# LcsNodes-Extension-GPIO-Board-32-S-B_00_.net
KiCad netlist of a schematic drawn in EasyEDA
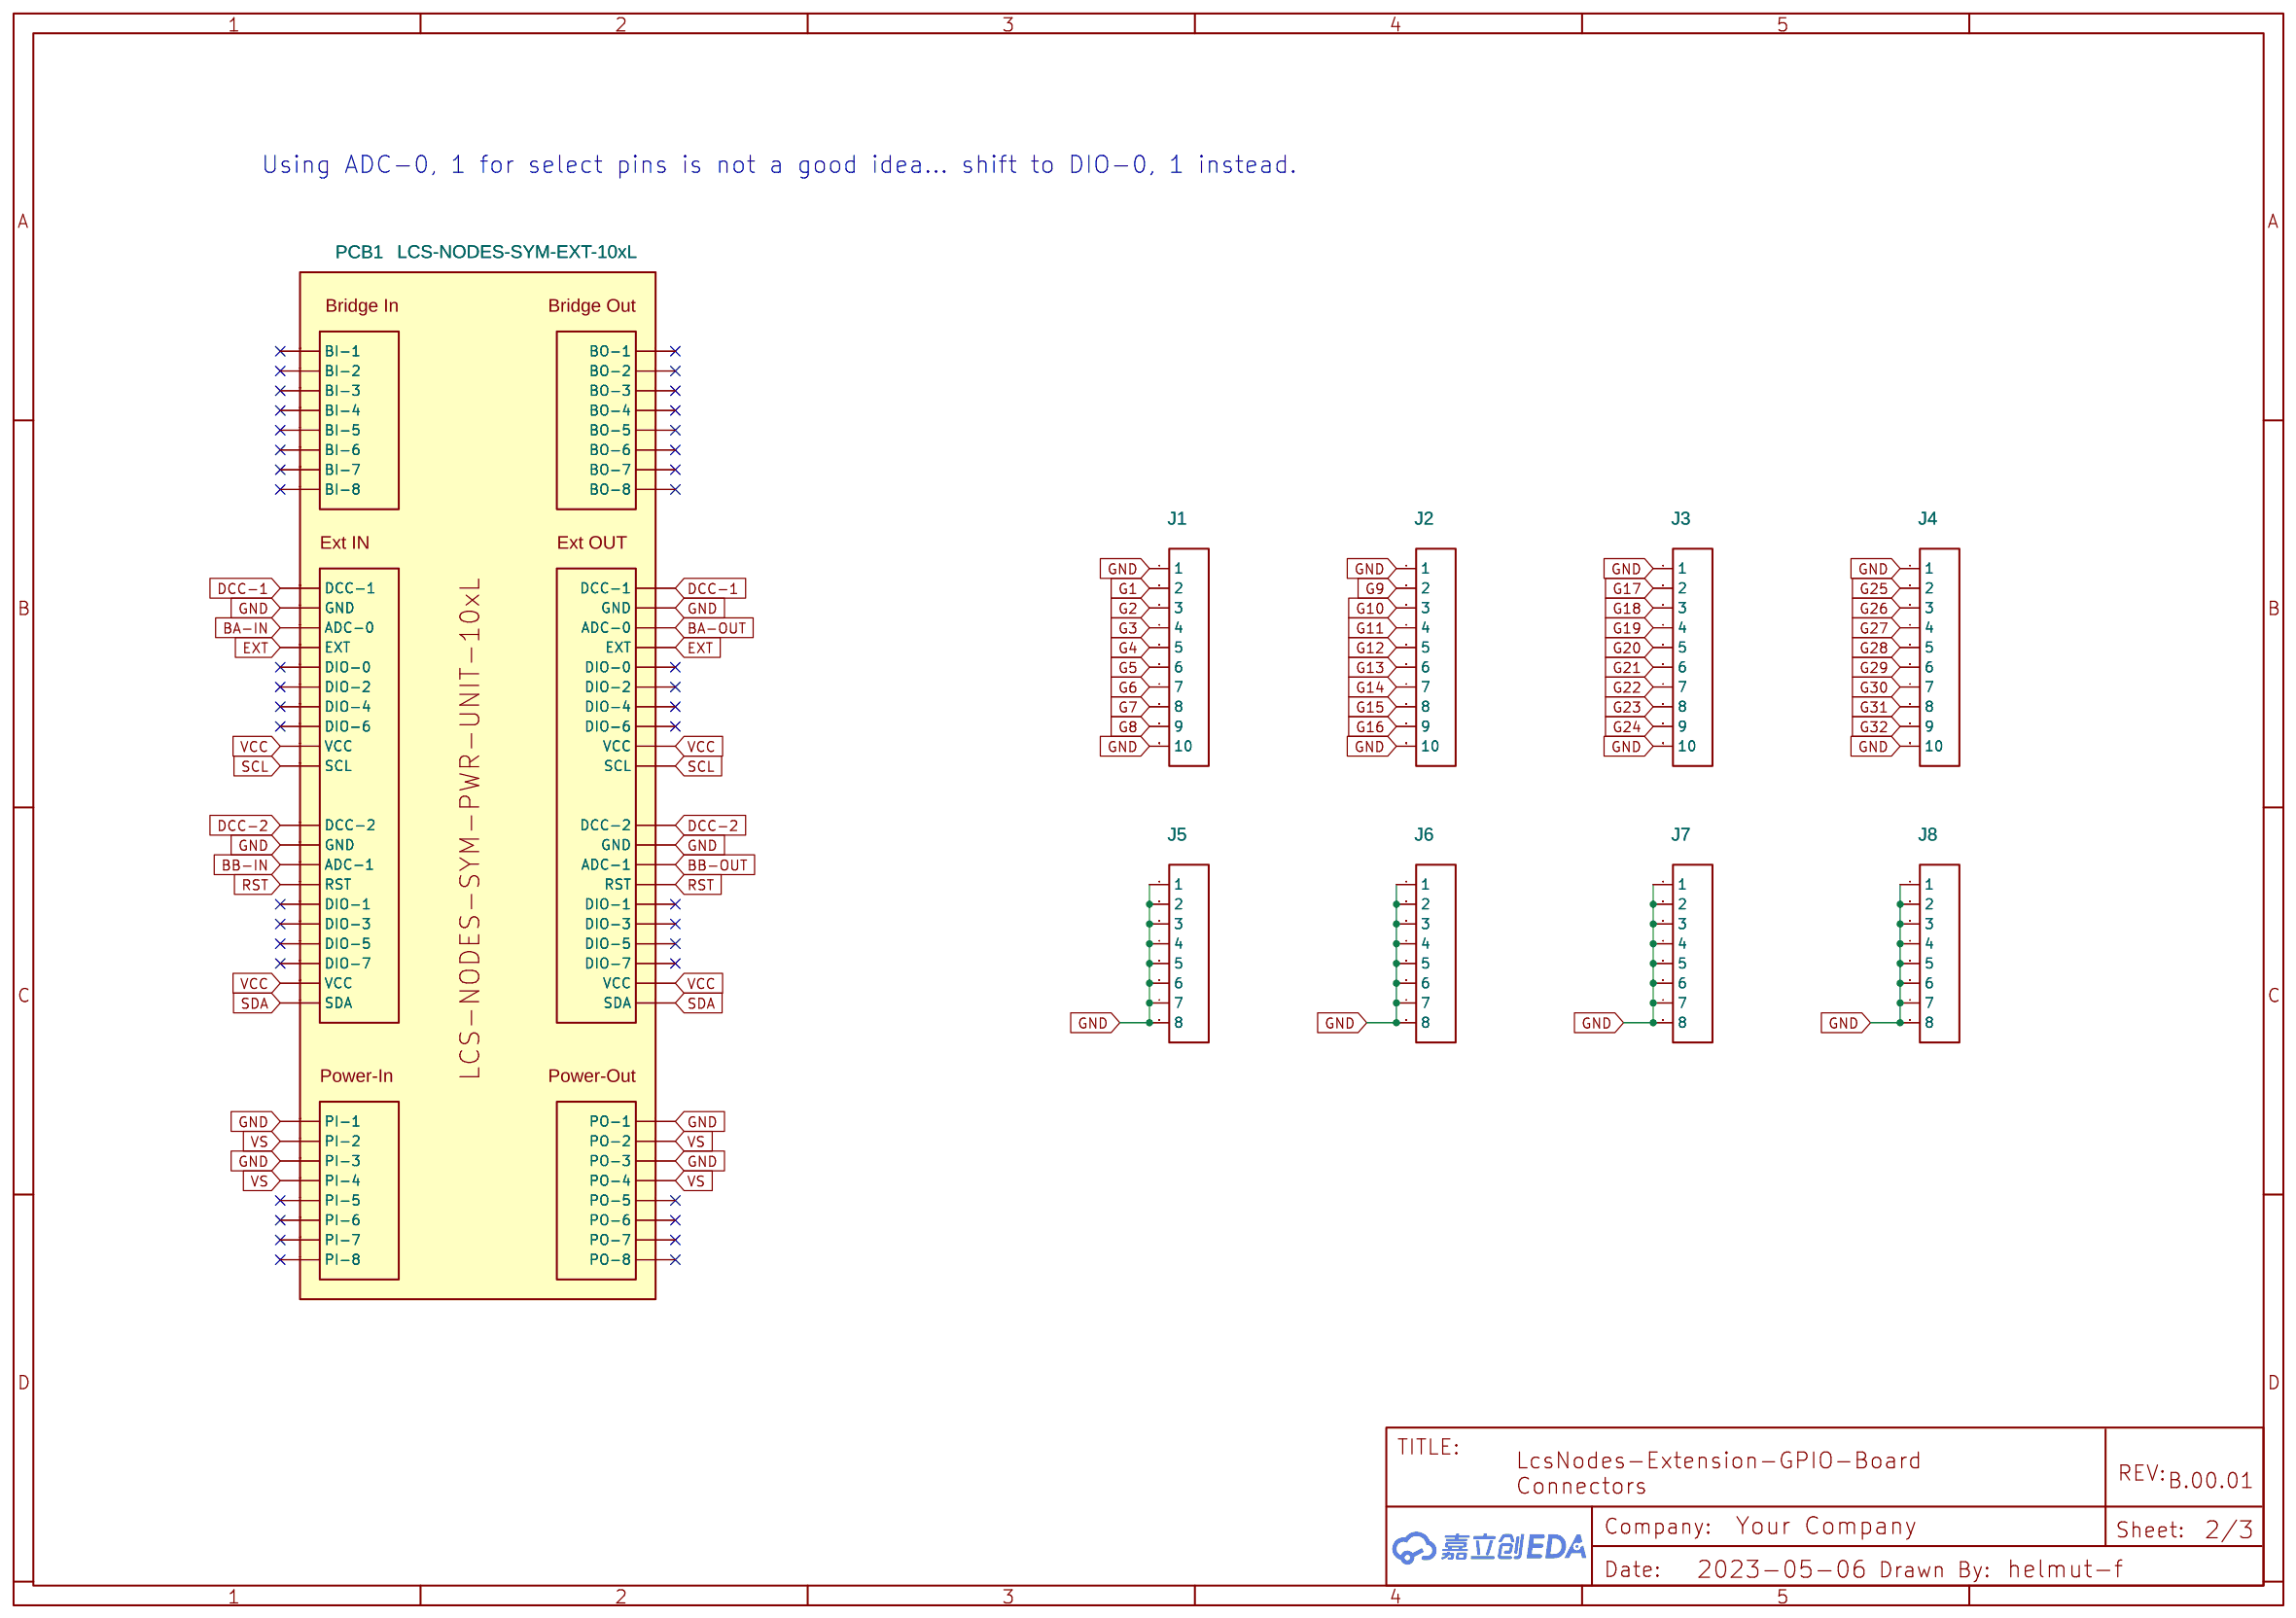
[diagram p0: Connectors]
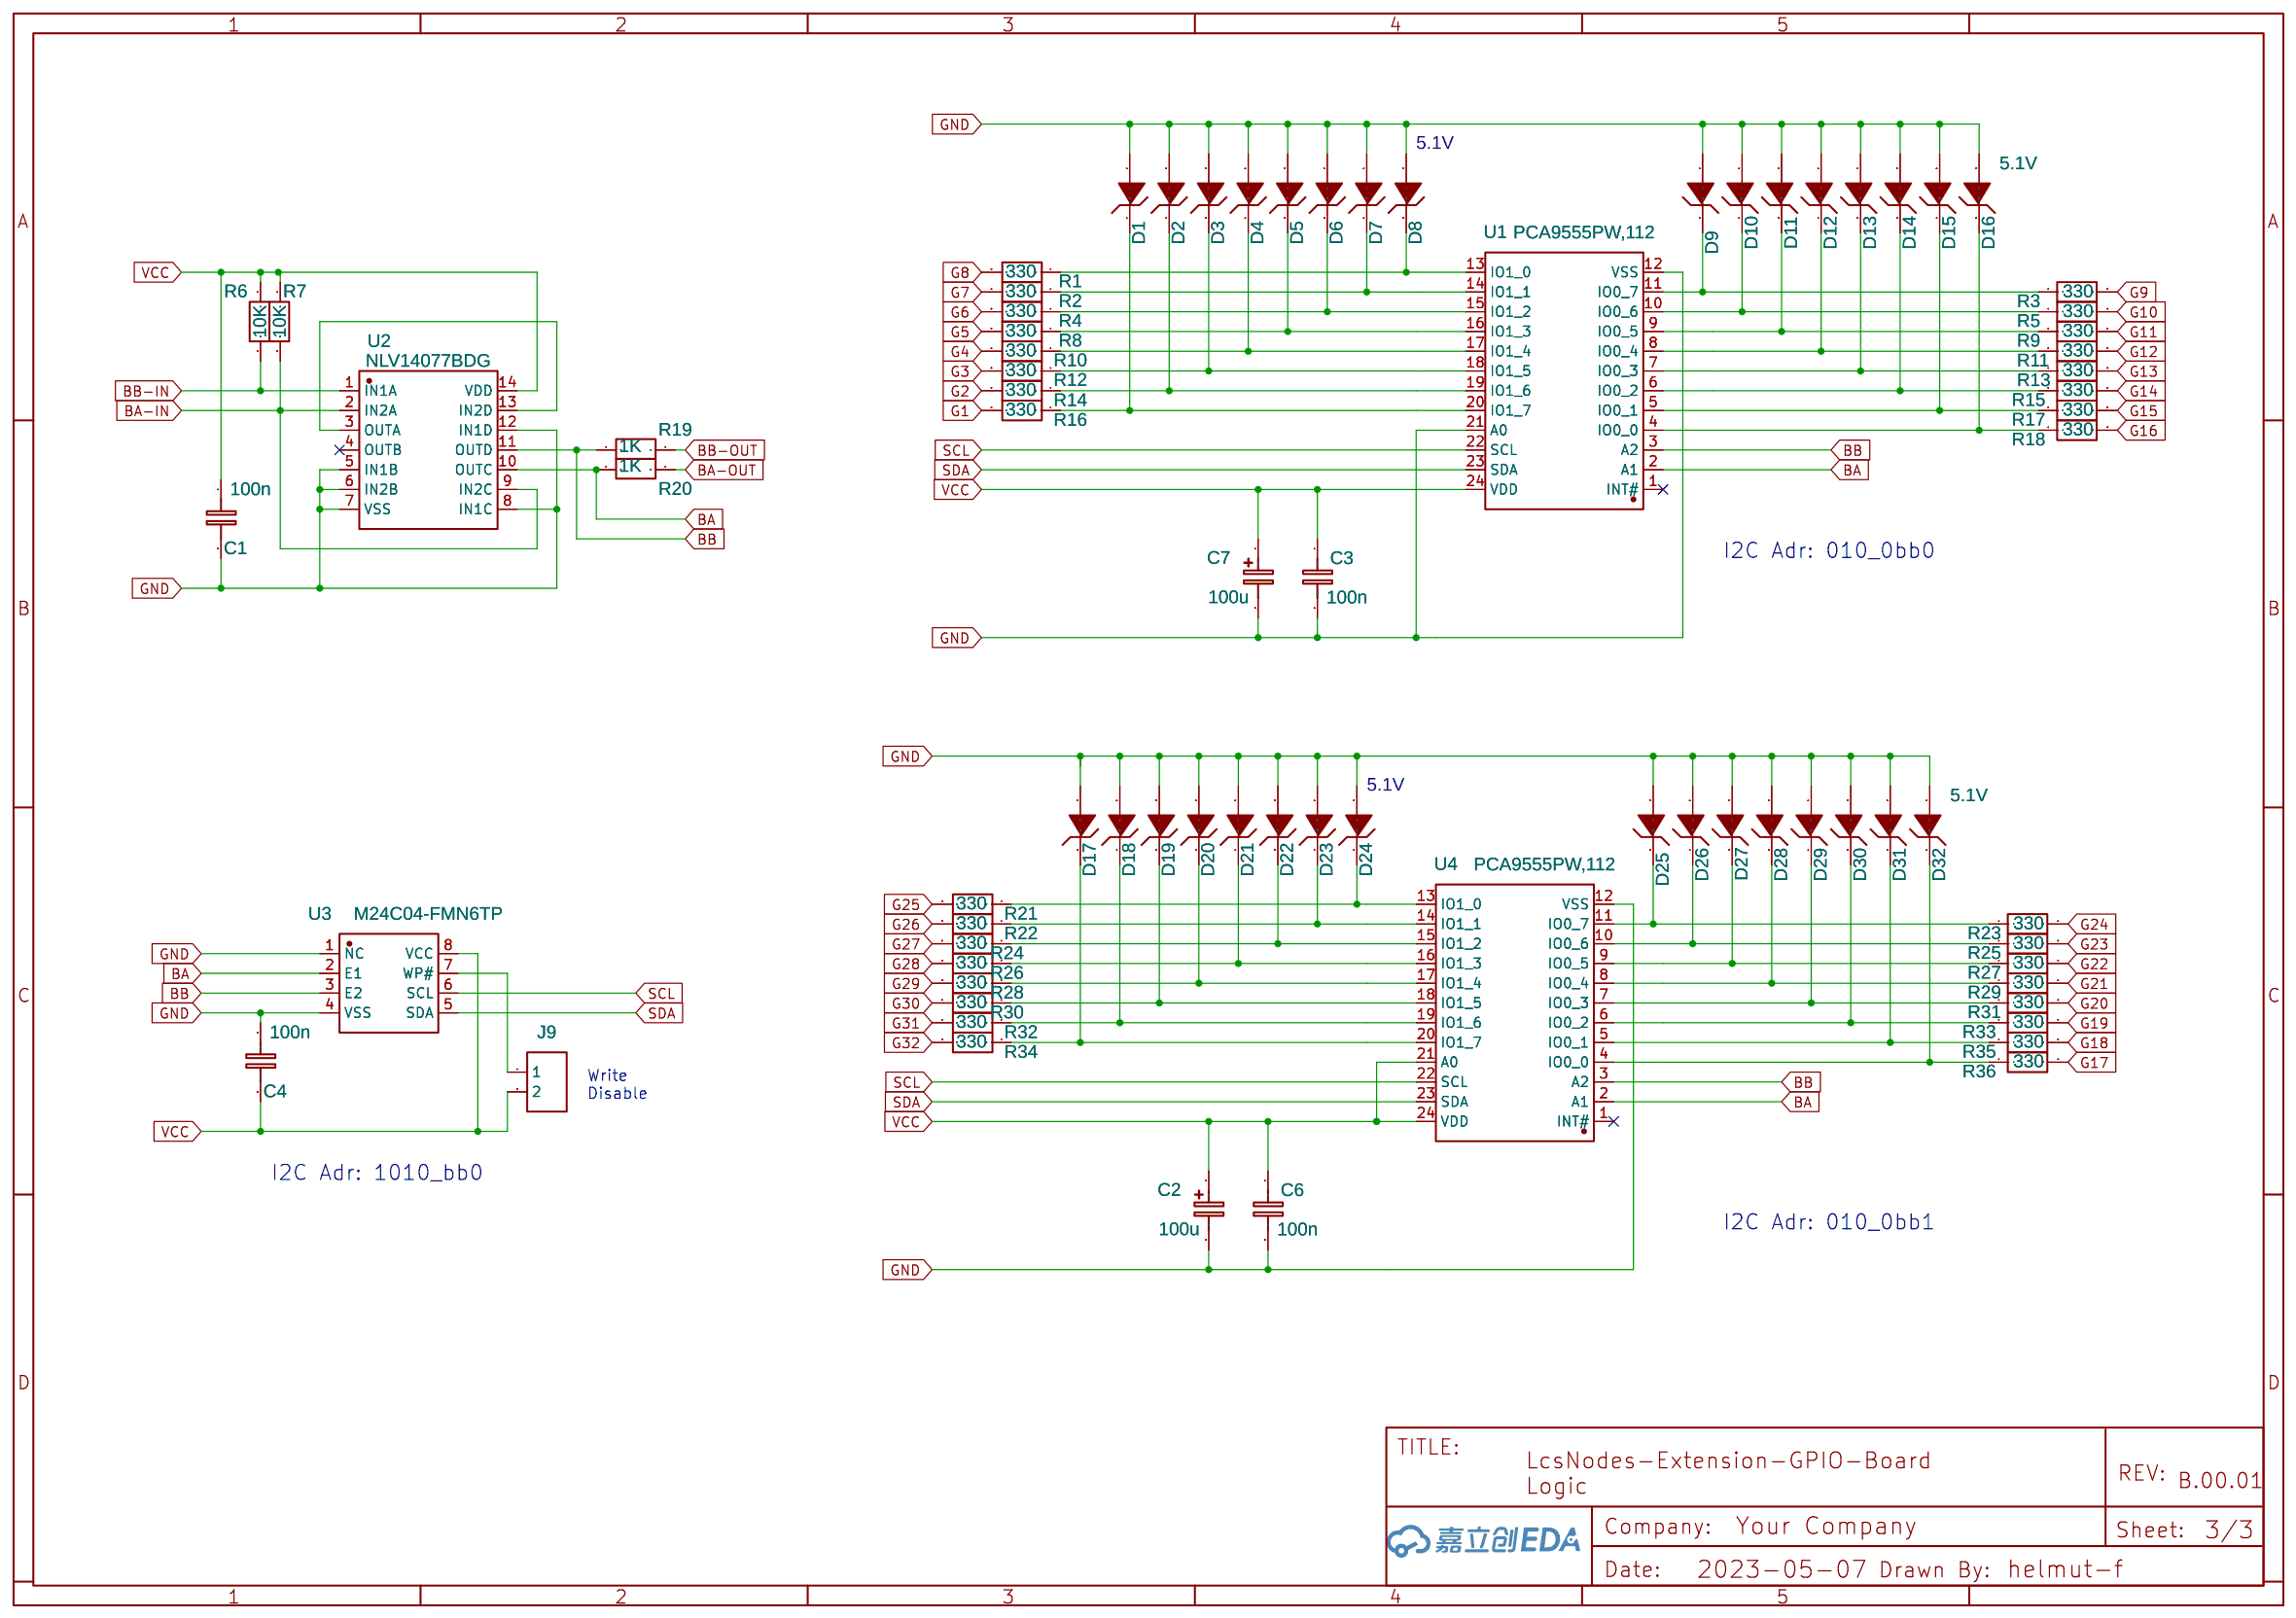
[diagram p1: Logic]
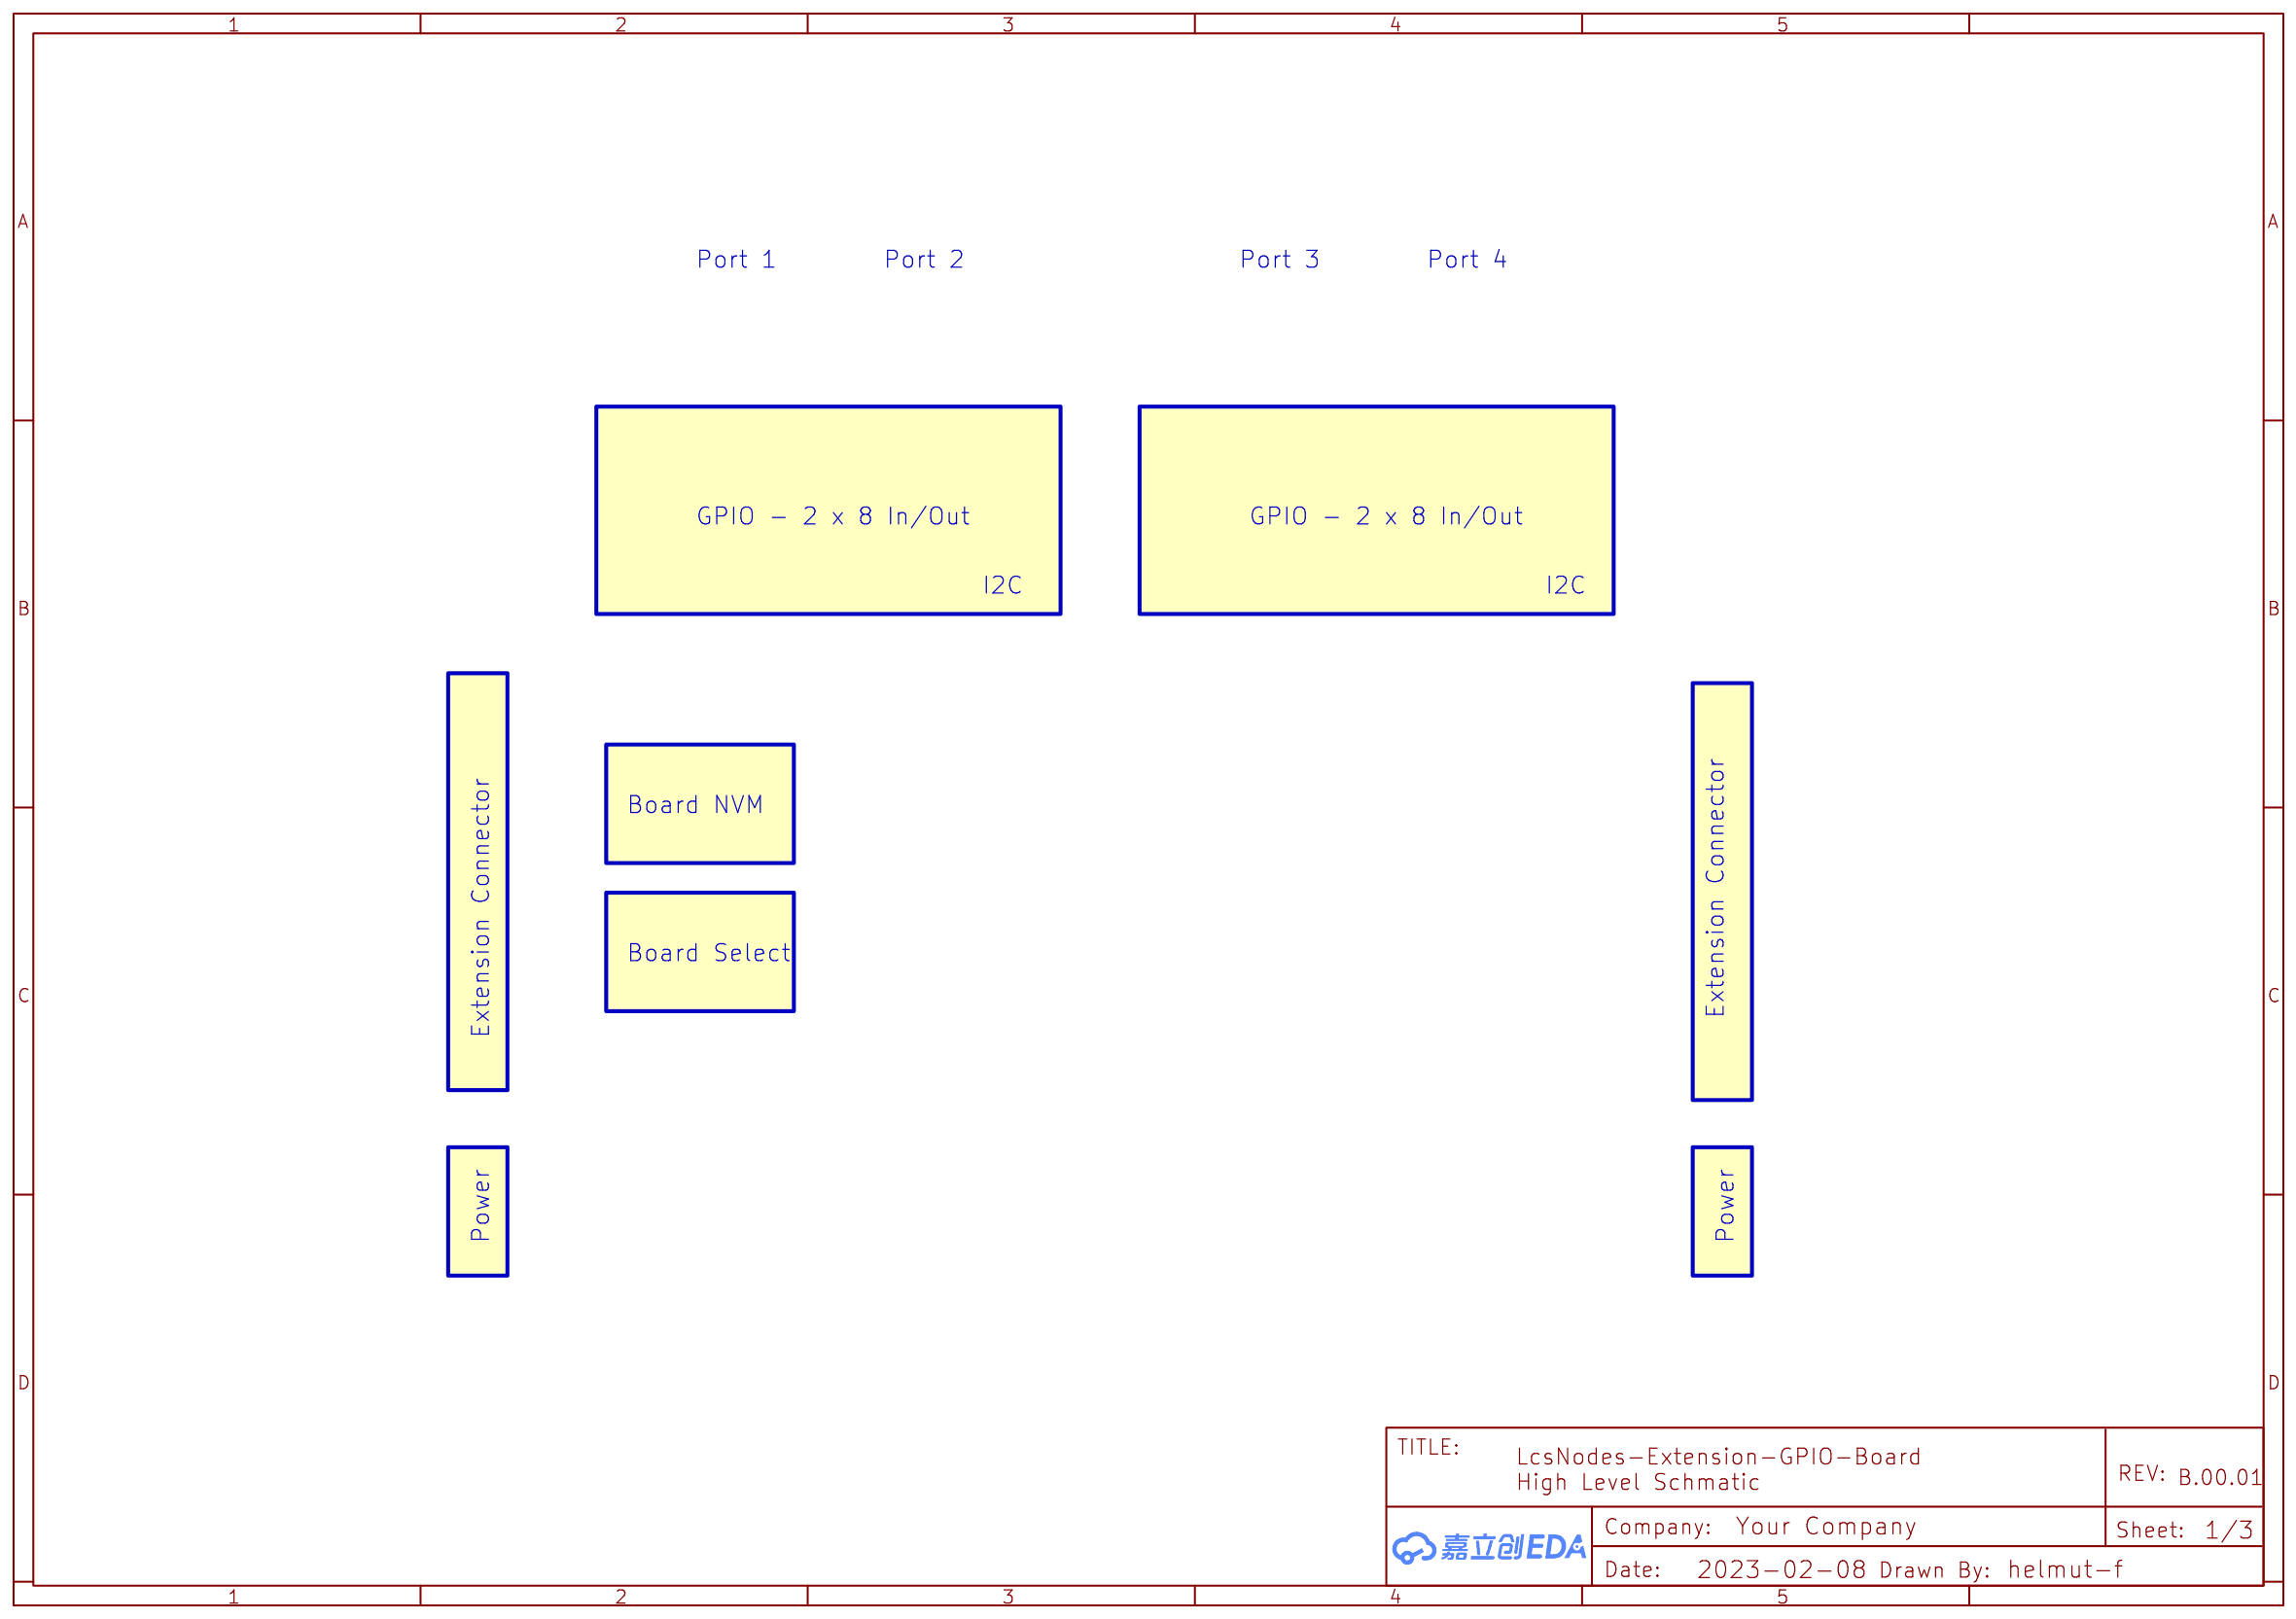
[diagram p2: High Level Schematic]

(export (version "E")
  (design (tool "Eeschema 10.0.6"))
  (components
    (comp (ref "J1") (value "HDR-M-2.54_1x10") (libsource (lib "") (part "HDR-M-2.54_1x10")))
    (comp (ref "J2") (value "HDR-M-2.54_1x10") (libsource (lib "") (part "HDR-M-2.54_1x10")))
    (comp (ref "J3") (value "HDR-M-2.54_1x10") (libsource (lib "") (part "HDR-M-2.54_1x10")))
    (comp (ref "J4") (value "HDR-M-2.54_1x10") (libsource (lib "") (part "HDR-M-2.54_1x10")))
    (comp (ref "J5") (value "HDR-M-2.54_1x8") (libsource (lib "") (part "HDR-M-2.54_1x8")))
    (comp (ref "J6") (value "HDR-M-2.54_1x8") (libsource (lib "") (part "HDR-M-2.54_1x8")))
    (comp (ref "J7") (value "HDR-M-2.54_1x8") (libsource (lib "") (part "HDR-M-2.54_1x8")))
    (comp (ref "J8") (value "HDR-M-2.54_1x8") (libsource (lib "") (part "HDR-M-2.54_1x8")))
    (comp (ref "PCB1") (value "LCS-NODES-SYM-EXT-10xL") (libsource (lib "") (part "LCS-NODES-SYM-EXT-10xL")))
    (comp (ref "C1") (value "100n") (libsource (lib "") (part "C_0603_EU_1")))
    (comp (ref "C2") (value "100u") (libsource (lib "") (part "CE_TH_D4.0×F1.5_EU")))
    (comp (ref "C3") (value "100n") (libsource (lib "") (part "C_0603_EU_1")))
    (comp (ref "C4") (value "100n") (libsource (lib "") (part "C_0603_EU")))
    (comp (ref "C6") (value "100n") (libsource (lib "") (part "C_0603_EU")))
    (comp (ref "C7") (value "100u") (libsource (lib "") (part "CE_TH_D4.0×F1.5_EU_1")))
    (comp (ref "D1")
      (value "5.1V")
      (fields (field (name "Manufacturer Part") "Diode Zener") (field (name "Manufacturer") "SEMTECH"))
      (libsource (lib "") (part "Diode Zener"))
    )
    (comp (ref "D2")
      (value "5.1V")
      (fields (field (name "Manufacturer Part") "Diode Zener") (field (name "Manufacturer") "SEMTECH"))
      (libsource (lib "") (part "Diode Zener"))
    )
    (comp (ref "D3")
      (value "5.1V")
      (fields (field (name "Manufacturer Part") "Diode Zener") (field (name "Manufacturer") "SEMTECH"))
      (libsource (lib "") (part "Diode Zener"))
    )
    (comp (ref "D4")
      (value "5.1V")
      (fields (field (name "Manufacturer Part") "Diode Zener") (field (name "Manufacturer") "SEMTECH"))
      (libsource (lib "") (part "Diode Zener"))
    )
    (comp (ref "D5")
      (value "5.1V")
      (fields (field (name "Manufacturer Part") "Diode Zener") (field (name "Manufacturer") "SEMTECH"))
      (libsource (lib "") (part "Diode Zener"))
    )
    (comp (ref "D6")
      (value "5.1V")
      (fields (field (name "Manufacturer Part") "Diode Zener") (field (name "Manufacturer") "SEMTECH"))
      (libsource (lib "") (part "Diode Zener"))
    )
    (comp (ref "D7")
      (value "5.1V")
      (fields (field (name "Manufacturer Part") "Diode Zener") (field (name "Manufacturer") "SEMTECH"))
      (libsource (lib "") (part "Diode Zener"))
    )
    (comp (ref "D8")
      (value "5.1V")
      (fields (field (name "Manufacturer Part") "Diode Zener") (field (name "Manufacturer") "SEMTECH"))
      (libsource (lib "") (part "Diode Zener"))
    )
    (comp (ref "D9")
      (value "5.1V")
      (fields (field (name "Manufacturer Part") "Diode Zener") (field (name "Manufacturer") "SEMTECH"))
      (libsource (lib "") (part "Diode Zener_1"))
    )
    (comp (ref "D10")
      (value "5.1V")
      (fields (field (name "Manufacturer Part") "Diode Zener") (field (name "Manufacturer") "SEMTECH"))
      (libsource (lib "") (part "Diode Zener_1"))
    )
    (comp (ref "D11")
      (value "5.1V")
      (fields (field (name "Manufacturer Part") "Diode Zener") (field (name "Manufacturer") "SEMTECH"))
      (libsource (lib "") (part "Diode Zener_1"))
    )
    (comp (ref "D12")
      (value "5.1V")
      (fields (field (name "Manufacturer Part") "Diode Zener") (field (name "Manufacturer") "SEMTECH"))
      (libsource (lib "") (part "Diode Zener_1"))
    )
    (comp (ref "D13")
      (value "5.1V")
      (fields (field (name "Manufacturer Part") "Diode Zener") (field (name "Manufacturer") "SEMTECH"))
      (libsource (lib "") (part "Diode Zener_1"))
    )
    (comp (ref "D14")
      (value "5.1V")
      (fields (field (name "Manufacturer Part") "Diode Zener") (field (name "Manufacturer") "SEMTECH"))
      (libsource (lib "") (part "Diode Zener_1"))
    )
    (comp (ref "D15")
      (value "5.1V")
      (fields (field (name "Manufacturer Part") "Diode Zener") (field (name "Manufacturer") "SEMTECH"))
      (libsource (lib "") (part "Diode Zener_1"))
    )
    (comp (ref "D16")
      (value "5.1V")
      (fields (field (name "Manufacturer Part") "Diode Zener") (field (name "Manufacturer") "SEMTECH"))
      (libsource (lib "") (part "Diode Zener_1"))
    )
    (comp (ref "D17")
      (value "5.1V")
      (fields (field (name "Manufacturer Part") "Diode Zener") (field (name "Manufacturer") "SEMTECH"))
      (libsource (lib "") (part "Diode Zener"))
    )
    (comp (ref "D18")
      (value "5.1V")
      (fields (field (name "Manufacturer Part") "Diode Zener") (field (name "Manufacturer") "SEMTECH"))
      (libsource (lib "") (part "Diode Zener"))
    )
    (comp (ref "D19")
      (value "5.1V")
      (fields (field (name "Manufacturer Part") "Diode Zener") (field (name "Manufacturer") "SEMTECH"))
      (libsource (lib "") (part "Diode Zener"))
    )
    (comp (ref "D20")
      (value "5.1V")
      (fields (field (name "Manufacturer Part") "Diode Zener") (field (name "Manufacturer") "SEMTECH"))
      (libsource (lib "") (part "Diode Zener"))
    )
    (comp (ref "D21")
      (value "5.1V")
      (fields (field (name "Manufacturer Part") "Diode Zener") (field (name "Manufacturer") "SEMTECH"))
      (libsource (lib "") (part "Diode Zener"))
    )
    (comp (ref "D22")
      (value "5.1V")
      (fields (field (name "Manufacturer Part") "Diode Zener") (field (name "Manufacturer") "SEMTECH"))
      (libsource (lib "") (part "Diode Zener"))
    )
    (comp (ref "D23")
      (value "5.1V")
      (fields (field (name "Manufacturer Part") "Diode Zener") (field (name "Manufacturer") "SEMTECH"))
      (libsource (lib "") (part "Diode Zener"))
    )
    (comp (ref "D24")
      (value "5.1V")
      (fields (field (name "Manufacturer Part") "Diode Zener") (field (name "Manufacturer") "SEMTECH"))
      (libsource (lib "") (part "Diode Zener"))
    )
    (comp (ref "D25")
      (value "5.1V")
      (fields (field (name "Manufacturer Part") "Diode Zener") (field (name "Manufacturer") "SEMTECH"))
      (libsource (lib "") (part "Diode Zener_1"))
    )
    (comp (ref "D26")
      (value "5.1V")
      (fields (field (name "Manufacturer Part") "Diode Zener") (field (name "Manufacturer") "SEMTECH"))
      (libsource (lib "") (part "Diode Zener_1"))
    )
    (comp (ref "D27")
      (value "5.1V")
      (fields (field (name "Manufacturer Part") "Diode Zener") (field (name "Manufacturer") "SEMTECH"))
      (libsource (lib "") (part "Diode Zener_1"))
    )
    (comp (ref "D28")
      (value "5.1V")
      (fields (field (name "Manufacturer Part") "Diode Zener") (field (name "Manufacturer") "SEMTECH"))
      (libsource (lib "") (part "Diode Zener_1"))
    )
    (comp (ref "D29")
      (value "5.1V")
      (fields (field (name "Manufacturer Part") "Diode Zener") (field (name "Manufacturer") "SEMTECH"))
      (libsource (lib "") (part "Diode Zener_1"))
    )
    (comp (ref "D30")
      (value "5.1V")
      (fields (field (name "Manufacturer Part") "Diode Zener") (field (name "Manufacturer") "SEMTECH"))
      (libsource (lib "") (part "Diode Zener_1"))
    )
    (comp (ref "D31")
      (value "5.1V")
      (fields (field (name "Manufacturer Part") "Diode Zener") (field (name "Manufacturer") "SEMTECH"))
      (libsource (lib "") (part "Diode Zener_1"))
    )
    (comp (ref "D32")
      (value "5.1V")
      (fields (field (name "Manufacturer Part") "Diode Zener") (field (name "Manufacturer") "SEMTECH"))
      (libsource (lib "") (part "Diode Zener_1"))
    )
    (comp (ref "J9") (value "HDR-M-2.54_1x2") (libsource (lib "") (part "HDR-M-2.54_1x2")))
    (comp (ref "R1") (value "330") (libsource (lib "") (part "R_AXIAL-0.3_EU_2")))
    (comp (ref "R2") (value "330") (libsource (lib "") (part "R_AXIAL-0.3_EU_2")))
    (comp (ref "R3") (value "330") (libsource (lib "") (part "R_AXIAL-0.3_EU_1")))
    (comp (ref "R4") (value "330") (libsource (lib "") (part "R_AXIAL-0.3_EU_2")))
    (comp (ref "R5") (value "330") (libsource (lib "") (part "R_AXIAL-0.3_EU_1")))
    (comp (ref "R6") (value "10K") (libsource (lib "") (part "R_AXIAL-0.3_EU")))
    (comp (ref "R7") (value "10K") (libsource (lib "") (part "R_AXIAL-0.3_EU")))
    (comp (ref "R8") (value "330") (libsource (lib "") (part "R_AXIAL-0.3_EU_2")))
    (comp (ref "R9") (value "330") (libsource (lib "") (part "R_AXIAL-0.3_EU_1")))
    (comp (ref "R10") (value "330") (libsource (lib "") (part "R_AXIAL-0.3_EU_2")))
    (comp (ref "R11") (value "330") (libsource (lib "") (part "R_AXIAL-0.3_EU_1")))
    (comp (ref "R12") (value "330") (libsource (lib "") (part "R_AXIAL-0.3_EU_2")))
    (comp (ref "R13") (value "330") (libsource (lib "") (part "R_AXIAL-0.3_EU_1")))
    (comp (ref "R14") (value "330") (libsource (lib "") (part "R_AXIAL-0.3_EU_2")))
    (comp (ref "R15") (value "330") (libsource (lib "") (part "R_AXIAL-0.3_EU_1")))
    (comp (ref "R16") (value "330") (libsource (lib "") (part "R_AXIAL-0.3_EU_2")))
    (comp (ref "R17") (value "330") (libsource (lib "") (part "R_AXIAL-0.3_EU_1")))
    (comp (ref "R18") (value "330") (libsource (lib "") (part "R_AXIAL-0.3_EU_1")))
    (comp (ref "R19") (value "1K") (libsource (lib "") (part "R_AXIAL-0.3_EU_3")))
    (comp (ref "R20") (value "1K") (libsource (lib "") (part "R_AXIAL-0.3_EU_3")))
    (comp (ref "R21") (value "330") (libsource (lib "") (part "R_AXIAL-0.3_EU_2")))
    (comp (ref "R22") (value "330") (libsource (lib "") (part "R_AXIAL-0.3_EU_2")))
    (comp (ref "R23") (value "330") (libsource (lib "") (part "R_AXIAL-0.3_EU_1")))
    (comp (ref "R24") (value "330") (libsource (lib "") (part "R_AXIAL-0.3_EU_2")))
    (comp (ref "R25") (value "330") (libsource (lib "") (part "R_AXIAL-0.3_EU_1")))
    (comp (ref "R26") (value "330") (libsource (lib "") (part "R_AXIAL-0.3_EU_2")))
    (comp (ref "R27") (value "330") (libsource (lib "") (part "R_AXIAL-0.3_EU_1")))
    (comp (ref "R28") (value "330") (libsource (lib "") (part "R_AXIAL-0.3_EU_2")))
    (comp (ref "R29") (value "330") (libsource (lib "") (part "R_AXIAL-0.3_EU_1")))
    (comp (ref "R30") (value "330") (libsource (lib "") (part "R_AXIAL-0.3_EU_2")))
    (comp (ref "R31") (value "330") (libsource (lib "") (part "R_AXIAL-0.3_EU_1")))
    (comp (ref "R32") (value "330") (libsource (lib "") (part "R_AXIAL-0.3_EU_2")))
    (comp (ref "R33") (value "330") (libsource (lib "") (part "R_AXIAL-0.3_EU_1")))
    (comp (ref "R34") (value "330") (libsource (lib "") (part "R_AXIAL-0.3_EU_2")))
    (comp (ref "R35") (value "330") (libsource (lib "") (part "R_AXIAL-0.3_EU_1")))
    (comp (ref "R36") (value "330") (libsource (lib "") (part "R_AXIAL-0.3_EU_1")))
    (comp (ref "U1")
      (value "PCA9555PW,112")
      (fields (field (name "Manufacturer") "NXP(恩智浦)"))
      (libsource (lib "") (part "PCA9555PW,112"))
    )
    (comp (ref "U2")
      (value "NLV14077BDG")
      (fields (field (name "Manufacturer") "onsemi(安森美)"))
      (libsource (lib "") (part "NLV14077BDG"))
    )
    (comp (ref "U3")
      (value "M24C04-FMN6TP")
      (fields (field (name "Manufacturer") "ST(意法半导体)"))
      (libsource (lib "") (part "M24C04-FMN6TP"))
    )
    (comp (ref "U4")
      (value "PCA9555PW,112")
      (fields (field (name "Manufacturer") "NXP(恩智浦)"))
      (libsource (lib "") (part "PCA9555PW,112"))
    )
  )
  (nets
    (net (code "1") (name "BA") (class "Default")
      (node (ref "R20") (pin "2") (pinfunction "2_2") (pintype "unspecified"))
      (node (ref "U1") (pin "2") (pinfunction "A1_2") (pintype "unspecified"))
      (node (ref "U2") (pin "10") (pinfunction "OUTC_10") (pintype "unspecified"))
      (node (ref "U3") (pin "2") (pinfunction "E1_2") (pintype "unspecified"))
      (node (ref "U4") (pin "2") (pinfunction "A1_2") (pintype "unspecified"))
    )
    (net (code "2") (name "BA-IN") (class "Default")
      (node (ref "PCB1") (pin "22") (pinfunction "ADC-0_22") (pintype "unspecified"))
      (node (ref "R7") (pin "2") (pinfunction "2_2") (pintype "unspecified"))
      (node (ref "U2") (pin "2") (pinfunction "IN2A_2") (pintype "unspecified"))
      (node (ref "U2") (pin "9") (pinfunction "IN2C_9") (pintype "unspecified"))
    )
    (net (code "3") (name "BA-OUT") (class "Default")
      (node (ref "PCB1") (pin "62") (pinfunction "ADC-0_62") (pintype "unspecified"))
      (node (ref "R20") (pin "1") (pinfunction "1_1") (pintype "unspecified"))
    )
    (net (code "4") (name "BB") (class "Default")
      (node (ref "R19") (pin "2") (pinfunction "2_2") (pintype "unspecified"))
      (node (ref "U1") (pin "3") (pinfunction "A2_3") (pintype "unspecified"))
      (node (ref "U2") (pin "11") (pinfunction "OUTD_11") (pintype "unspecified"))
      (node (ref "U3") (pin "3") (pinfunction "E2_3") (pintype "unspecified"))
      (node (ref "U4") (pin "3") (pinfunction "A2_3") (pintype "unspecified"))
    )
    (net (code "5") (name "BB-IN") (class "Default")
      (node (ref "PCB1") (pin "32") (pinfunction "ADC-1_32") (pintype "unspecified"))
      (node (ref "R6") (pin "2") (pinfunction "2_2") (pintype "unspecified"))
      (node (ref "U2") (pin "1") (pinfunction "IN1A_1") (pintype "unspecified"))
    )
    (net (code "6") (name "BB-OUT") (class "Default")
      (node (ref "PCB1") (pin "72") (pinfunction "ADC-1_72") (pintype "unspecified"))
      (node (ref "R19") (pin "1") (pinfunction "1_1") (pintype "unspecified"))
    )
    (net (code "7") (name "DCC-1") (class "Default")
      (node (ref "PCB1") (pin "20") (pinfunction "DCC-1_20") (pintype "unspecified"))
      (node (ref "PCB1") (pin "60") (pinfunction "DCC-1_60") (pintype "unspecified"))
    )
    (net (code "8") (name "DCC-2") (class "Default")
      (node (ref "PCB1") (pin "30") (pinfunction "DCC-2_30") (pintype "unspecified"))
      (node (ref "PCB1") (pin "70") (pinfunction "DCC-2_70") (pintype "unspecified"))
    )
    (net (code "9") (name "EXT") (class "Default")
      (node (ref "PCB1") (pin "23") (pinfunction "EXT_23") (pintype "unspecified"))
      (node (ref "PCB1") (pin "63") (pinfunction "EXT_63") (pintype "unspecified"))
    )
    (net (code "10") (name "G1") (class "Default")
      (node (ref "J1") (pin "2") (pinfunction "2_2") (pintype "unspecified"))
      (node (ref "R16") (pin "2") (pinfunction "2_2") (pintype "unspecified"))
    )
    (net (code "11") (name "G2") (class "Default")
      (node (ref "J1") (pin "3") (pinfunction "3_3") (pintype "unspecified"))
      (node (ref "R14") (pin "2") (pinfunction "2_2") (pintype "unspecified"))
    )
    (net (code "12") (name "G3") (class "Default")
      (node (ref "J1") (pin "4") (pinfunction "4_4") (pintype "unspecified"))
      (node (ref "R12") (pin "2") (pinfunction "2_2") (pintype "unspecified"))
    )
    (net (code "13") (name "G4") (class "Default")
      (node (ref "J1") (pin "5") (pinfunction "5_5") (pintype "unspecified"))
      (node (ref "R10") (pin "2") (pinfunction "2_2") (pintype "unspecified"))
    )
    (net (code "14") (name "G5") (class "Default")
      (node (ref "J1") (pin "6") (pinfunction "6_6") (pintype "unspecified"))
      (node (ref "R8") (pin "2") (pinfunction "2_2") (pintype "unspecified"))
    )
    (net (code "15") (name "G6") (class "Default")
      (node (ref "J1") (pin "7") (pinfunction "7_7") (pintype "unspecified"))
      (node (ref "R4") (pin "2") (pinfunction "2_2") (pintype "unspecified"))
    )
    (net (code "16") (name "G7") (class "Default")
      (node (ref "J1") (pin "8") (pinfunction "8_8") (pintype "unspecified"))
      (node (ref "R2") (pin "2") (pinfunction "2_2") (pintype "unspecified"))
    )
    (net (code "17") (name "G8") (class "Default")
      (node (ref "J1") (pin "9") (pinfunction "9_9") (pintype "unspecified"))
      (node (ref "R1") (pin "2") (pinfunction "2_2") (pintype "unspecified"))
    )
    (net (code "18") (name "G9") (class "Default")
      (node (ref "J2") (pin "2") (pinfunction "2_2") (pintype "unspecified"))
      (node (ref "R3") (pin "2") (pinfunction "2_2") (pintype "unspecified"))
    )
    (net (code "19") (name "G10") (class "Default")
      (node (ref "J2") (pin "3") (pinfunction "3_3") (pintype "unspecified"))
      (node (ref "R5") (pin "2") (pinfunction "2_2") (pintype "unspecified"))
    )
    (net (code "20") (name "G11") (class "Default")
      (node (ref "J2") (pin "4") (pinfunction "4_4") (pintype "unspecified"))
      (node (ref "R9") (pin "2") (pinfunction "2_2") (pintype "unspecified"))
    )
    (net (code "21") (name "G12") (class "Default")
      (node (ref "J2") (pin "5") (pinfunction "5_5") (pintype "unspecified"))
      (node (ref "R11") (pin "2") (pinfunction "2_2") (pintype "unspecified"))
    )
    (net (code "22") (name "G13") (class "Default")
      (node (ref "J2") (pin "6") (pinfunction "6_6") (pintype "unspecified"))
      (node (ref "R13") (pin "2") (pinfunction "2_2") (pintype "unspecified"))
    )
    (net (code "23") (name "G14") (class "Default")
      (node (ref "J2") (pin "7") (pinfunction "7_7") (pintype "unspecified"))
      (node (ref "R15") (pin "2") (pinfunction "2_2") (pintype "unspecified"))
    )
    (net (code "24") (name "G15") (class "Default")
      (node (ref "J2") (pin "8") (pinfunction "8_8") (pintype "unspecified"))
      (node (ref "R17") (pin "2") (pinfunction "2_2") (pintype "unspecified"))
    )
    (net (code "25") (name "G16") (class "Default")
      (node (ref "J2") (pin "9") (pinfunction "9_9") (pintype "unspecified"))
      (node (ref "R18") (pin "2") (pinfunction "2_2") (pintype "unspecified"))
    )
    (net (code "26") (name "G17") (class "Default")
      (node (ref "J3") (pin "2") (pinfunction "2_2") (pintype "unspecified"))
      (node (ref "R36") (pin "2") (pinfunction "2_2") (pintype "unspecified"))
    )
    (net (code "27") (name "G18") (class "Default")
      (node (ref "J3") (pin "3") (pinfunction "3_3") (pintype "unspecified"))
      (node (ref "R35") (pin "2") (pinfunction "2_2") (pintype "unspecified"))
    )
    (net (code "28") (name "G19") (class "Default")
      (node (ref "J3") (pin "4") (pinfunction "4_4") (pintype "unspecified"))
      (node (ref "R33") (pin "2") (pinfunction "2_2") (pintype "unspecified"))
    )
    (net (code "29") (name "G20") (class "Default")
      (node (ref "J3") (pin "5") (pinfunction "5_5") (pintype "unspecified"))
      (node (ref "R31") (pin "2") (pinfunction "2_2") (pintype "unspecified"))
    )
    (net (code "30") (name "G21") (class "Default")
      (node (ref "J3") (pin "6") (pinfunction "6_6") (pintype "unspecified"))
      (node (ref "R29") (pin "2") (pinfunction "2_2") (pintype "unspecified"))
    )
    (net (code "31") (name "G22") (class "Default")
      (node (ref "J3") (pin "7") (pinfunction "7_7") (pintype "unspecified"))
      (node (ref "R27") (pin "2") (pinfunction "2_2") (pintype "unspecified"))
    )
    (net (code "32") (name "G23") (class "Default")
      (node (ref "J3") (pin "8") (pinfunction "8_8") (pintype "unspecified"))
      (node (ref "R25") (pin "2") (pinfunction "2_2") (pintype "unspecified"))
    )
    (net (code "33") (name "G24") (class "Default")
      (node (ref "J3") (pin "9") (pinfunction "9_9") (pintype "unspecified"))
      (node (ref "R23") (pin "2") (pinfunction "2_2") (pintype "unspecified"))
    )
    (net (code "34") (name "G25") (class "Default")
      (node (ref "J4") (pin "2") (pinfunction "2_2") (pintype "unspecified"))
      (node (ref "R21") (pin "2") (pinfunction "2_2") (pintype "unspecified"))
    )
    (net (code "35") (name "G26") (class "Default")
      (node (ref "J4") (pin "3") (pinfunction "3_3") (pintype "unspecified"))
      (node (ref "R22") (pin "2") (pinfunction "2_2") (pintype "unspecified"))
    )
    (net (code "36") (name "G27") (class "Default")
      (node (ref "J4") (pin "4") (pinfunction "4_4") (pintype "unspecified"))
      (node (ref "R24") (pin "2") (pinfunction "2_2") (pintype "unspecified"))
    )
    (net (code "37") (name "G28") (class "Default")
      (node (ref "J4") (pin "5") (pinfunction "5_5") (pintype "unspecified"))
      (node (ref "R26") (pin "2") (pinfunction "2_2") (pintype "unspecified"))
    )
    (net (code "38") (name "G29") (class "Default")
      (node (ref "J4") (pin "6") (pinfunction "6_6") (pintype "unspecified"))
      (node (ref "R28") (pin "2") (pinfunction "2_2") (pintype "unspecified"))
    )
    (net (code "39") (name "G30") (class "Default")
      (node (ref "J4") (pin "7") (pinfunction "7_7") (pintype "unspecified"))
      (node (ref "R30") (pin "2") (pinfunction "2_2") (pintype "unspecified"))
    )
    (net (code "40") (name "G31") (class "Default")
      (node (ref "J4") (pin "8") (pinfunction "8_8") (pintype "unspecified"))
      (node (ref "R32") (pin "2") (pinfunction "2_2") (pintype "unspecified"))
    )
    (net (code "41") (name "G32") (class "Default")
      (node (ref "J4") (pin "9") (pinfunction "9_9") (pintype "unspecified"))
      (node (ref "R34") (pin "2") (pinfunction "2_2") (pintype "unspecified"))
    )
    (net (code "42") (name "GND") (class "Default")
      (node (ref "C1") (pin "2") (pinfunction "2_2") (pintype "unspecified"))
      (node (ref "C2") (pin "2") (pinfunction "2_2") (pintype "unspecified"))
      (node (ref "C3") (pin "2") (pinfunction "2_2") (pintype "unspecified"))
      (node (ref "C4") (pin "1") (pinfunction "1_1") (pintype "unspecified"))
      (node (ref "C6") (pin "2") (pinfunction "2_2") (pintype "unspecified"))
      (node (ref "C7") (pin "2") (pinfunction "2_2") (pintype "unspecified"))
      (node (ref "D1") (pin "2") (pinfunction "A_2") (pintype "unspecified"))
      (node (ref "D10") (pin "2") (pinfunction "A_2") (pintype "unspecified"))
      (node (ref "D11") (pin "2") (pinfunction "A_2") (pintype "unspecified"))
      (node (ref "D12") (pin "2") (pinfunction "A_2") (pintype "unspecified"))
      (node (ref "D13") (pin "2") (pinfunction "A_2") (pintype "unspecified"))
      (node (ref "D14") (pin "2") (pinfunction "A_2") (pintype "unspecified"))
      (node (ref "D15") (pin "2") (pinfunction "A_2") (pintype "unspecified"))
      (node (ref "D16") (pin "2") (pinfunction "A_2") (pintype "unspecified"))
      (node (ref "D17") (pin "2") (pinfunction "A_2") (pintype "unspecified"))
      (node (ref "D18") (pin "2") (pinfunction "A_2") (pintype "unspecified"))
      (node (ref "D19") (pin "2") (pinfunction "A_2") (pintype "unspecified"))
      (node (ref "D2") (pin "2") (pinfunction "A_2") (pintype "unspecified"))
      (node (ref "D20") (pin "2") (pinfunction "A_2") (pintype "unspecified"))
      (node (ref "D21") (pin "2") (pinfunction "A_2") (pintype "unspecified"))
      (node (ref "D22") (pin "2") (pinfunction "A_2") (pintype "unspecified"))
      (node (ref "D23") (pin "2") (pinfunction "A_2") (pintype "unspecified"))
      (node (ref "D24") (pin "2") (pinfunction "A_2") (pintype "unspecified"))
      (node (ref "D25") (pin "2") (pinfunction "A_2") (pintype "unspecified"))
      (node (ref "D26") (pin "2") (pinfunction "A_2") (pintype "unspecified"))
      (node (ref "D27") (pin "2") (pinfunction "A_2") (pintype "unspecified"))
      (node (ref "D28") (pin "2") (pinfunction "A_2") (pintype "unspecified"))
      (node (ref "D29") (pin "2") (pinfunction "A_2") (pintype "unspecified"))
      (node (ref "D3") (pin "2") (pinfunction "A_2") (pintype "unspecified"))
      (node (ref "D30") (pin "2") (pinfunction "A_2") (pintype "unspecified"))
      (node (ref "D31") (pin "2") (pinfunction "A_2") (pintype "unspecified"))
      (node (ref "D32") (pin "2") (pinfunction "A_2") (pintype "unspecified"))
      (node (ref "D4") (pin "2") (pinfunction "A_2") (pintype "unspecified"))
      (node (ref "D5") (pin "2") (pinfunction "A_2") (pintype "unspecified"))
      (node (ref "D6") (pin "2") (pinfunction "A_2") (pintype "unspecified"))
      (node (ref "D7") (pin "2") (pinfunction "A_2") (pintype "unspecified"))
      (node (ref "D8") (pin "2") (pinfunction "A_2") (pintype "unspecified"))
      (node (ref "D9") (pin "2") (pinfunction "A_2") (pintype "unspecified"))
      (node (ref "J1") (pin "1") (pinfunction "1_1") (pintype "unspecified"))
      (node (ref "J1") (pin "10") (pinfunction "10_10") (pintype "unspecified"))
      (node (ref "J2") (pin "1") (pinfunction "1_1") (pintype "unspecified"))
      (node (ref "J2") (pin "10") (pinfunction "10_10") (pintype "unspecified"))
      (node (ref "J3") (pin "1") (pinfunction "1_1") (pintype "unspecified"))
      (node (ref "J3") (pin "10") (pinfunction "10_10") (pintype "unspecified"))
      (node (ref "J4") (pin "1") (pinfunction "1_1") (pintype "unspecified"))
      (node (ref "J4") (pin "10") (pinfunction "10_10") (pintype "unspecified"))
      (node (ref "J5") (pin "1") (pinfunction "1_1") (pintype "unspecified"))
      (node (ref "J5") (pin "2") (pinfunction "2_2") (pintype "unspecified"))
      (node (ref "J5") (pin "3") (pinfunction "3_3") (pintype "unspecified"))
      (node (ref "J5") (pin "4") (pinfunction "4_4") (pintype "unspecified"))
      (node (ref "J5") (pin "5") (pinfunction "5_5") (pintype "unspecified"))
      (node (ref "J5") (pin "6") (pinfunction "6_6") (pintype "unspecified"))
      (node (ref "J5") (pin "7") (pinfunction "7_7") (pintype "unspecified"))
      (node (ref "J5") (pin "8") (pinfunction "8_8") (pintype "unspecified"))
      (node (ref "J6") (pin "1") (pinfunction "1_1") (pintype "unspecified"))
      (node (ref "J6") (pin "2") (pinfunction "2_2") (pintype "unspecified"))
      (node (ref "J6") (pin "3") (pinfunction "3_3") (pintype "unspecified"))
      (node (ref "J6") (pin "4") (pinfunction "4_4") (pintype "unspecified"))
      (node (ref "J6") (pin "5") (pinfunction "5_5") (pintype "unspecified"))
      (node (ref "J6") (pin "6") (pinfunction "6_6") (pintype "unspecified"))
      (node (ref "J6") (pin "7") (pinfunction "7_7") (pintype "unspecified"))
      (node (ref "J6") (pin "8") (pinfunction "8_8") (pintype "unspecified"))
      (node (ref "J7") (pin "1") (pinfunction "1_1") (pintype "unspecified"))
      (node (ref "J7") (pin "2") (pinfunction "2_2") (pintype "unspecified"))
      (node (ref "J7") (pin "3") (pinfunction "3_3") (pintype "unspecified"))
      (node (ref "J7") (pin "4") (pinfunction "4_4") (pintype "unspecified"))
      (node (ref "J7") (pin "5") (pinfunction "5_5") (pintype "unspecified"))
      (node (ref "J7") (pin "6") (pinfunction "6_6") (pintype "unspecified"))
      (node (ref "J7") (pin "7") (pinfunction "7_7") (pintype "unspecified"))
      (node (ref "J7") (pin "8") (pinfunction "8_8") (pintype "unspecified"))
      (node (ref "J8") (pin "1") (pinfunction "1_1") (pintype "unspecified"))
      (node (ref "J8") (pin "2") (pinfunction "2_2") (pintype "unspecified"))
      (node (ref "J8") (pin "3") (pinfunction "3_3") (pintype "unspecified"))
      (node (ref "J8") (pin "4") (pinfunction "4_4") (pintype "unspecified"))
      (node (ref "J8") (pin "5") (pinfunction "5_5") (pintype "unspecified"))
      (node (ref "J8") (pin "6") (pinfunction "6_6") (pintype "unspecified"))
      (node (ref "J8") (pin "7") (pinfunction "7_7") (pintype "unspecified"))
      (node (ref "J8") (pin "8") (pinfunction "8_8") (pintype "unspecified"))
      (node (ref "PCB1") (pin "21") (pinfunction "GND_21") (pintype "unspecified"))
      (node (ref "PCB1") (pin "31") (pinfunction "GND_31") (pintype "unspecified"))
      (node (ref "PCB1") (pin "40") (pinfunction "PI-1_40") (pintype "unspecified"))
      (node (ref "PCB1") (pin "42") (pinfunction "PI-3_42") (pintype "unspecified"))
      (node (ref "PCB1") (pin "61") (pinfunction "GND_61") (pintype "unspecified"))
      (node (ref "PCB1") (pin "71") (pinfunction "GND_71") (pintype "unspecified"))
      (node (ref "PCB1") (pin "80") (pinfunction "PO-1_80") (pintype "unspecified"))
      (node (ref "PCB1") (pin "82") (pinfunction "PO-3_82") (pintype "unspecified"))
      (node (ref "U1") (pin "12") (pinfunction "VSS_12") (pintype "unspecified"))
      (node (ref "U1") (pin "21") (pinfunction "A0_21") (pintype "unspecified"))
      (node (ref "U2") (pin "12") (pinfunction "IN1D_12") (pintype "unspecified"))
      (node (ref "U2") (pin "5") (pinfunction "IN1B_5") (pintype "unspecified"))
      (node (ref "U2") (pin "6") (pinfunction "IN2B_6") (pintype "unspecified"))
      (node (ref "U2") (pin "7") (pinfunction "VSS_7") (pintype "unspecified"))
      (node (ref "U2") (pin "8") (pinfunction "IN1C_8") (pintype "unspecified"))
      (node (ref "U3") (pin "1") (pinfunction "NC_1") (pintype "unspecified"))
      (node (ref "U3") (pin "4") (pinfunction "VSS_4") (pintype "unspecified"))
      (node (ref "U4") (pin "12") (pinfunction "VSS_12") (pintype "unspecified"))
    )
    (net (code "43") (name "Net-(D1-C)") (class "Default")
      (node (ref "D1") (pin "1") (pinfunction "C_1") (pintype "unspecified"))
      (node (ref "R16") (pin "1") (pinfunction "1_1") (pintype "unspecified"))
      (node (ref "U1") (pin "20") (pinfunction "IO1_7_20") (pintype "unspecified"))
    )
    (net (code "44") (name "Net-(D2-C)") (class "Default")
      (node (ref "D2") (pin "1") (pinfunction "C_1") (pintype "unspecified"))
      (node (ref "R14") (pin "1") (pinfunction "1_1") (pintype "unspecified"))
      (node (ref "U1") (pin "19") (pinfunction "IO1_6_19") (pintype "unspecified"))
    )
    (net (code "45") (name "Net-(D3-C)") (class "Default")
      (node (ref "D3") (pin "1") (pinfunction "C_1") (pintype "unspecified"))
      (node (ref "R12") (pin "1") (pinfunction "1_1") (pintype "unspecified"))
      (node (ref "U1") (pin "18") (pinfunction "IO1_5_18") (pintype "unspecified"))
    )
    (net (code "46") (name "Net-(D4-C)") (class "Default")
      (node (ref "D4") (pin "1") (pinfunction "C_1") (pintype "unspecified"))
      (node (ref "R10") (pin "1") (pinfunction "1_1") (pintype "unspecified"))
      (node (ref "U1") (pin "17") (pinfunction "IO1_4_17") (pintype "unspecified"))
    )
    (net (code "47") (name "Net-(D5-C)") (class "Default")
      (node (ref "D5") (pin "1") (pinfunction "C_1") (pintype "unspecified"))
      (node (ref "R8") (pin "1") (pinfunction "1_1") (pintype "unspecified"))
      (node (ref "U1") (pin "16") (pinfunction "IO1_3_16") (pintype "unspecified"))
    )
    (net (code "48") (name "Net-(D6-C)") (class "Default")
      (node (ref "D6") (pin "1") (pinfunction "C_1") (pintype "unspecified"))
      (node (ref "R4") (pin "1") (pinfunction "1_1") (pintype "unspecified"))
      (node (ref "U1") (pin "15") (pinfunction "IO1_2_15") (pintype "unspecified"))
    )
    (net (code "49") (name "Net-(D7-C)") (class "Default")
      (node (ref "D7") (pin "1") (pinfunction "C_1") (pintype "unspecified"))
      (node (ref "R2") (pin "1") (pinfunction "1_1") (pintype "unspecified"))
      (node (ref "U1") (pin "14") (pinfunction "IO1_1_14") (pintype "unspecified"))
    )
    (net (code "50") (name "Net-(D8-C)") (class "Default")
      (node (ref "D8") (pin "1") (pinfunction "C_1") (pintype "unspecified"))
      (node (ref "R1") (pin "1") (pinfunction "1_1") (pintype "unspecified"))
      (node (ref "U1") (pin "13") (pinfunction "IO1_0_13") (pintype "unspecified"))
    )
    (net (code "51") (name "Net-(D9-C)") (class "Default")
      (node (ref "D9") (pin "1") (pinfunction "C_1") (pintype "unspecified"))
      (node (ref "R3") (pin "1") (pinfunction "1_1") (pintype "unspecified"))
      (node (ref "U1") (pin "11") (pinfunction "IO0_7_11") (pintype "unspecified"))
    )
    (net (code "52") (name "Net-(D10-C)") (class "Default")
      (node (ref "D10") (pin "1") (pinfunction "C_1") (pintype "unspecified"))
      (node (ref "R5") (pin "1") (pinfunction "1_1") (pintype "unspecified"))
      (node (ref "U1") (pin "10") (pinfunction "IO0_6_10") (pintype "unspecified"))
    )
    (net (code "53") (name "Net-(D11-C)") (class "Default")
      (node (ref "D11") (pin "1") (pinfunction "C_1") (pintype "unspecified"))
      (node (ref "R9") (pin "1") (pinfunction "1_1") (pintype "unspecified"))
      (node (ref "U1") (pin "9") (pinfunction "IO0_5_9") (pintype "unspecified"))
    )
    (net (code "54") (name "Net-(D12-C)") (class "Default")
      (node (ref "D12") (pin "1") (pinfunction "C_1") (pintype "unspecified"))
      (node (ref "R11") (pin "1") (pinfunction "1_1") (pintype "unspecified"))
      (node (ref "U1") (pin "8") (pinfunction "IO0_4_8") (pintype "unspecified"))
    )
    (net (code "55") (name "Net-(D13-C)") (class "Default")
      (node (ref "D13") (pin "1") (pinfunction "C_1") (pintype "unspecified"))
      (node (ref "R13") (pin "1") (pinfunction "1_1") (pintype "unspecified"))
      (node (ref "U1") (pin "7") (pinfunction "IO0_3_7") (pintype "unspecified"))
    )
    (net (code "56") (name "Net-(D14-C)") (class "Default")
      (node (ref "D14") (pin "1") (pinfunction "C_1") (pintype "unspecified"))
      (node (ref "R15") (pin "1") (pinfunction "1_1") (pintype "unspecified"))
      (node (ref "U1") (pin "6") (pinfunction "IO0_2_6") (pintype "unspecified"))
    )
    (net (code "57") (name "Net-(D15-C)") (class "Default")
      (node (ref "D15") (pin "1") (pinfunction "C_1") (pintype "unspecified"))
      (node (ref "R17") (pin "1") (pinfunction "1_1") (pintype "unspecified"))
      (node (ref "U1") (pin "5") (pinfunction "IO0_1_5") (pintype "unspecified"))
    )
    (net (code "58") (name "Net-(D16-C)") (class "Default")
      (node (ref "D16") (pin "1") (pinfunction "C_1") (pintype "unspecified"))
      (node (ref "R18") (pin "1") (pinfunction "1_1") (pintype "unspecified"))
      (node (ref "U1") (pin "4") (pinfunction "IO0_0_4") (pintype "unspecified"))
    )
    (net (code "59") (name "Net-(D17-C)") (class "Default")
      (node (ref "D17") (pin "1") (pinfunction "C_1") (pintype "unspecified"))
      (node (ref "R34") (pin "1") (pinfunction "1_1") (pintype "unspecified"))
      (node (ref "U4") (pin "20") (pinfunction "IO1_7_20") (pintype "unspecified"))
    )
    (net (code "60") (name "Net-(D18-C)") (class "Default")
      (node (ref "D18") (pin "1") (pinfunction "C_1") (pintype "unspecified"))
      (node (ref "R32") (pin "1") (pinfunction "1_1") (pintype "unspecified"))
      (node (ref "U4") (pin "19") (pinfunction "IO1_6_19") (pintype "unspecified"))
    )
    (net (code "61") (name "Net-(D19-C)") (class "Default")
      (node (ref "D19") (pin "1") (pinfunction "C_1") (pintype "unspecified"))
      (node (ref "R30") (pin "1") (pinfunction "1_1") (pintype "unspecified"))
      (node (ref "U4") (pin "18") (pinfunction "IO1_5_18") (pintype "unspecified"))
    )
    (net (code "62") (name "Net-(D20-C)") (class "Default")
      (node (ref "D20") (pin "1") (pinfunction "C_1") (pintype "unspecified"))
      (node (ref "R28") (pin "1") (pinfunction "1_1") (pintype "unspecified"))
      (node (ref "U4") (pin "17") (pinfunction "IO1_4_17") (pintype "unspecified"))
    )
    (net (code "63") (name "Net-(D21-C)") (class "Default")
      (node (ref "D21") (pin "1") (pinfunction "C_1") (pintype "unspecified"))
      (node (ref "R26") (pin "1") (pinfunction "1_1") (pintype "unspecified"))
      (node (ref "U4") (pin "16") (pinfunction "IO1_3_16") (pintype "unspecified"))
    )
    (net (code "64") (name "Net-(D22-C)") (class "Default")
      (node (ref "D22") (pin "1") (pinfunction "C_1") (pintype "unspecified"))
      (node (ref "R24") (pin "1") (pinfunction "1_1") (pintype "unspecified"))
      (node (ref "U4") (pin "15") (pinfunction "IO1_2_15") (pintype "unspecified"))
    )
    (net (code "65") (name "Net-(D23-C)") (class "Default")
      (node (ref "D23") (pin "1") (pinfunction "C_1") (pintype "unspecified"))
      (node (ref "R22") (pin "1") (pinfunction "1_1") (pintype "unspecified"))
      (node (ref "U4") (pin "14") (pinfunction "IO1_1_14") (pintype "unspecified"))
    )
    (net (code "66") (name "Net-(D24-C)") (class "Default")
      (node (ref "D24") (pin "1") (pinfunction "C_1") (pintype "unspecified"))
      (node (ref "R21") (pin "1") (pinfunction "1_1") (pintype "unspecified"))
      (node (ref "U4") (pin "13") (pinfunction "IO1_0_13") (pintype "unspecified"))
    )
    (net (code "67") (name "Net-(D25-C)") (class "Default")
      (node (ref "D25") (pin "1") (pinfunction "C_1") (pintype "unspecified"))
      (node (ref "R23") (pin "1") (pinfunction "1_1") (pintype "unspecified"))
      (node (ref "U4") (pin "11") (pinfunction "IO0_7_11") (pintype "unspecified"))
    )
    (net (code "68") (name "Net-(D26-C)") (class "Default")
      (node (ref "D26") (pin "1") (pinfunction "C_1") (pintype "unspecified"))
      (node (ref "R25") (pin "1") (pinfunction "1_1") (pintype "unspecified"))
      (node (ref "U4") (pin "10") (pinfunction "IO0_6_10") (pintype "unspecified"))
    )
    (net (code "69") (name "Net-(D27-C)") (class "Default")
      (node (ref "D27") (pin "1") (pinfunction "C_1") (pintype "unspecified"))
      (node (ref "R27") (pin "1") (pinfunction "1_1") (pintype "unspecified"))
      (node (ref "U4") (pin "9") (pinfunction "IO0_5_9") (pintype "unspecified"))
    )
    (net (code "70") (name "Net-(D28-C)") (class "Default")
      (node (ref "D28") (pin "1") (pinfunction "C_1") (pintype "unspecified"))
      (node (ref "R29") (pin "1") (pinfunction "1_1") (pintype "unspecified"))
      (node (ref "U4") (pin "8") (pinfunction "IO0_4_8") (pintype "unspecified"))
    )
    (net (code "71") (name "Net-(D29-C)") (class "Default")
      (node (ref "D29") (pin "1") (pinfunction "C_1") (pintype "unspecified"))
      (node (ref "R31") (pin "1") (pinfunction "1_1") (pintype "unspecified"))
      (node (ref "U4") (pin "7") (pinfunction "IO0_3_7") (pintype "unspecified"))
    )
    (net (code "72") (name "Net-(D30-C)") (class "Default")
      (node (ref "D30") (pin "1") (pinfunction "C_1") (pintype "unspecified"))
      (node (ref "R33") (pin "1") (pinfunction "1_1") (pintype "unspecified"))
      (node (ref "U4") (pin "6") (pinfunction "IO0_2_6") (pintype "unspecified"))
    )
    (net (code "73") (name "Net-(D31-C)") (class "Default")
      (node (ref "D31") (pin "1") (pinfunction "C_1") (pintype "unspecified"))
      (node (ref "R35") (pin "1") (pinfunction "1_1") (pintype "unspecified"))
      (node (ref "U4") (pin "5") (pinfunction "IO0_1_5") (pintype "unspecified"))
    )
    (net (code "74") (name "Net-(D32-C)") (class "Default")
      (node (ref "D32") (pin "1") (pinfunction "C_1") (pintype "unspecified"))
      (node (ref "R36") (pin "1") (pinfunction "1_1") (pintype "unspecified"))
      (node (ref "U4") (pin "4") (pinfunction "IO0_0_4") (pintype "unspecified"))
    )
    (net (code "75") (name "Net-(U2-IN2D)") (class "Default")
      (node (ref "U2") (pin "13") (pinfunction "IN2D_13") (pintype "unspecified"))
      (node (ref "U2") (pin "3") (pinfunction "OUTA_3") (pintype "unspecified"))
    )
    (net (code "76") (name "Net-(U3-WP#)") (class "Default")
      (node (ref "J9") (pin "1") (pinfunction "1_1") (pintype "unspecified"))
      (node (ref "U3") (pin "7") (pinfunction "WP#_7") (pintype "unspecified"))
    )
    (net (code "77") (name "RST") (class "Default")
      (node (ref "PCB1") (pin "33") (pinfunction "RST_33") (pintype "unspecified"))
      (node (ref "PCB1") (pin "73") (pinfunction "RST_73") (pintype "unspecified"))
    )
    (net (code "78") (name "SCL") (class "Default")
      (node (ref "PCB1") (pin "29") (pinfunction "SCL_29") (pintype "unspecified"))
      (node (ref "PCB1") (pin "69") (pinfunction "SCL_69") (pintype "unspecified"))
      (node (ref "U1") (pin "22") (pinfunction "SCL_22") (pintype "unspecified"))
      (node (ref "U3") (pin "6") (pinfunction "SCL_6") (pintype "unspecified"))
      (node (ref "U4") (pin "22") (pinfunction "SCL_22") (pintype "unspecified"))
    )
    (net (code "79") (name "SDA") (class "Default")
      (node (ref "PCB1") (pin "39") (pinfunction "SDA_39") (pintype "unspecified"))
      (node (ref "PCB1") (pin "79") (pinfunction "SDA_79") (pintype "unspecified"))
      (node (ref "U1") (pin "23") (pinfunction "SDA_23") (pintype "unspecified"))
      (node (ref "U3") (pin "5") (pinfunction "SDA_5") (pintype "unspecified"))
      (node (ref "U4") (pin "23") (pinfunction "SDA_23") (pintype "unspecified"))
    )
    (net (code "80") (name "VCC") (class "Default")
      (node (ref "C1") (pin "1") (pinfunction "1_1") (pintype "unspecified"))
      (node (ref "C2") (pin "1") (pinfunction "1_1") (pintype "unspecified"))
      (node (ref "C3") (pin "1") (pinfunction "1_1") (pintype "unspecified"))
      (node (ref "C4") (pin "2") (pinfunction "2_2") (pintype "unspecified"))
      (node (ref "C6") (pin "1") (pinfunction "1_1") (pintype "unspecified"))
      (node (ref "C7") (pin "1") (pinfunction "1_1") (pintype "unspecified"))
      (node (ref "J9") (pin "2") (pinfunction "2_2") (pintype "unspecified"))
      (node (ref "PCB1") (pin "28") (pinfunction "VCC_28") (pintype "unspecified"))
      (node (ref "PCB1") (pin "38") (pinfunction "VCC_38") (pintype "unspecified"))
      (node (ref "PCB1") (pin "68") (pinfunction "VCC_68") (pintype "unspecified"))
      (node (ref "PCB1") (pin "78") (pinfunction "VCC_78") (pintype "unspecified"))
      (node (ref "R6") (pin "1") (pinfunction "1_1") (pintype "unspecified"))
      (node (ref "R7") (pin "1") (pinfunction "1_1") (pintype "unspecified"))
      (node (ref "U1") (pin "24") (pinfunction "VDD_24") (pintype "unspecified"))
      (node (ref "U2") (pin "14") (pinfunction "VDD_14") (pintype "unspecified"))
      (node (ref "U3") (pin "8") (pinfunction "VCC_8") (pintype "unspecified"))
      (node (ref "U4") (pin "21") (pinfunction "A0_21") (pintype "unspecified"))
      (node (ref "U4") (pin "24") (pinfunction "VDD_24") (pintype "unspecified"))
    )
    (net (code "81") (name "VS") (class "Default")
      (node (ref "PCB1") (pin "41") (pinfunction "PI-2_41") (pintype "unspecified"))
      (node (ref "PCB1") (pin "43") (pinfunction "PI-4_43") (pintype "unspecified"))
      (node (ref "PCB1") (pin "81") (pinfunction "PO-2_81") (pintype "unspecified"))
      (node (ref "PCB1") (pin "83") (pinfunction "PO-4_83") (pintype "unspecified"))
    )
    (net (code "82") (name "unconnected-(PCB1-BI-1-Pad10)") (class "Default")
      (node (ref "PCB1") (pin "10") (pinfunction "BI-1_10") (pintype "unspecified+no_connect"))
    )
    (net (code "83") (name "unconnected-(PCB1-BI-2-Pad11)") (class "Default")
      (node (ref "PCB1") (pin "11") (pinfunction "BI-2_11") (pintype "unspecified+no_connect"))
    )
    (net (code "84") (name "unconnected-(PCB1-BI-3-Pad12)") (class "Default")
      (node (ref "PCB1") (pin "12") (pinfunction "BI-3_12") (pintype "unspecified+no_connect"))
    )
    (net (code "85") (name "unconnected-(PCB1-BI-4-Pad13)") (class "Default")
      (node (ref "PCB1") (pin "13") (pinfunction "BI-4_13") (pintype "unspecified+no_connect"))
    )
    (net (code "86") (name "unconnected-(PCB1-BI-5-Pad14)") (class "Default")
      (node (ref "PCB1") (pin "14") (pinfunction "BI-5_14") (pintype "unspecified+no_connect"))
    )
    (net (code "87") (name "unconnected-(PCB1-BI-6-Pad15)") (class "Default")
      (node (ref "PCB1") (pin "15") (pinfunction "BI-6_15") (pintype "unspecified+no_connect"))
    )
    (net (code "88") (name "unconnected-(PCB1-BI-7-Pad16)") (class "Default")
      (node (ref "PCB1") (pin "16") (pinfunction "BI-7_16") (pintype "unspecified+no_connect"))
    )
    (net (code "89") (name "unconnected-(PCB1-BI-8-Pad17)") (class "Default")
      (node (ref "PCB1") (pin "17") (pinfunction "BI-8_17") (pintype "unspecified+no_connect"))
    )
    (net (code "90") (name "unconnected-(PCB1-BO-1-Pad50)") (class "Default")
      (node (ref "PCB1") (pin "50") (pinfunction "BO-1_50") (pintype "unspecified+no_connect"))
    )
    (net (code "91") (name "unconnected-(PCB1-BO-2-Pad51)") (class "Default")
      (node (ref "PCB1") (pin "51") (pinfunction "BO-2_51") (pintype "unspecified+no_connect"))
    )
    (net (code "92") (name "unconnected-(PCB1-BO-3-Pad52)") (class "Default")
      (node (ref "PCB1") (pin "52") (pinfunction "BO-3_52") (pintype "unspecified+no_connect"))
    )
    (net (code "93") (name "unconnected-(PCB1-BO-4-Pad53)") (class "Default")
      (node (ref "PCB1") (pin "53") (pinfunction "BO-4_53") (pintype "unspecified+no_connect"))
    )
    (net (code "94") (name "unconnected-(PCB1-BO-5-Pad54)") (class "Default")
      (node (ref "PCB1") (pin "54") (pinfunction "BO-5_54") (pintype "unspecified+no_connect"))
    )
    (net (code "95") (name "unconnected-(PCB1-BO-6-Pad55)") (class "Default")
      (node (ref "PCB1") (pin "55") (pinfunction "BO-6_55") (pintype "unspecified+no_connect"))
    )
    (net (code "96") (name "unconnected-(PCB1-BO-7-Pad56)") (class "Default")
      (node (ref "PCB1") (pin "56") (pinfunction "BO-7_56") (pintype "unspecified+no_connect"))
    )
    (net (code "97") (name "unconnected-(PCB1-BO-8-Pad57)") (class "Default")
      (node (ref "PCB1") (pin "57") (pinfunction "BO-8_57") (pintype "unspecified+no_connect"))
    )
    (net (code "98") (name "unconnected-(PCB1-DIO-0-Pad24)") (class "Default")
      (node (ref "PCB1") (pin "24") (pinfunction "DIO-0_24") (pintype "unspecified+no_connect"))
    )
    (net (code "99") (name "unconnected-(PCB1-DIO-0-Pad64)") (class "Default")
      (node (ref "PCB1") (pin "64") (pinfunction "DIO-0_64") (pintype "unspecified+no_connect"))
    )
    (net (code "100") (name "unconnected-(PCB1-DIO-1-Pad34)") (class "Default")
      (node (ref "PCB1") (pin "34") (pinfunction "DIO-1_34") (pintype "unspecified+no_connect"))
    )
    (net (code "101") (name "unconnected-(PCB1-DIO-1-Pad74)") (class "Default")
      (node (ref "PCB1") (pin "74") (pinfunction "DIO-1_74") (pintype "unspecified+no_connect"))
    )
    (net (code "102") (name "unconnected-(PCB1-DIO-2-Pad25)") (class "Default")
      (node (ref "PCB1") (pin "25") (pinfunction "DIO-2_25") (pintype "unspecified+no_connect"))
    )
    (net (code "103") (name "unconnected-(PCB1-DIO-2-Pad65)") (class "Default")
      (node (ref "PCB1") (pin "65") (pinfunction "DIO-2_65") (pintype "unspecified+no_connect"))
    )
    (net (code "104") (name "unconnected-(PCB1-DIO-3-Pad35)") (class "Default")
      (node (ref "PCB1") (pin "35") (pinfunction "DIO-3_35") (pintype "unspecified+no_connect"))
    )
    (net (code "105") (name "unconnected-(PCB1-DIO-3-Pad75)") (class "Default")
      (node (ref "PCB1") (pin "75") (pinfunction "DIO-3_75") (pintype "unspecified+no_connect"))
    )
    (net (code "106") (name "unconnected-(PCB1-DIO-4-Pad26)") (class "Default")
      (node (ref "PCB1") (pin "26") (pinfunction "DIO-4_26") (pintype "unspecified+no_connect"))
    )
    (net (code "107") (name "unconnected-(PCB1-DIO-4-Pad66)") (class "Default")
      (node (ref "PCB1") (pin "66") (pinfunction "DIO-4_66") (pintype "unspecified+no_connect"))
    )
    (net (code "108") (name "unconnected-(PCB1-DIO-5-Pad36)") (class "Default")
      (node (ref "PCB1") (pin "36") (pinfunction "DIO-5_36") (pintype "unspecified+no_connect"))
    )
    (net (code "109") (name "unconnected-(PCB1-DIO-5-Pad76)") (class "Default")
      (node (ref "PCB1") (pin "76") (pinfunction "DIO-5_76") (pintype "unspecified+no_connect"))
    )
    (net (code "110") (name "unconnected-(PCB1-DIO-6-Pad27)") (class "Default")
      (node (ref "PCB1") (pin "27") (pinfunction "DIO-6_27") (pintype "unspecified+no_connect"))
    )
    (net (code "111") (name "unconnected-(PCB1-DIO-6-Pad67)") (class "Default")
      (node (ref "PCB1") (pin "67") (pinfunction "DIO-6_67") (pintype "unspecified+no_connect"))
    )
    (net (code "112") (name "unconnected-(PCB1-DIO-7-Pad37)") (class "Default")
      (node (ref "PCB1") (pin "37") (pinfunction "DIO-7_37") (pintype "unspecified+no_connect"))
    )
    (net (code "113") (name "unconnected-(PCB1-DIO-7-Pad77)") (class "Default")
      (node (ref "PCB1") (pin "77") (pinfunction "DIO-7_77") (pintype "unspecified+no_connect"))
    )
    (net (code "114") (name "unconnected-(PCB1-PI-5-Pad44)") (class "Default")
      (node (ref "PCB1") (pin "44") (pinfunction "PI-5_44") (pintype "unspecified+no_connect"))
    )
    (net (code "115") (name "unconnected-(PCB1-PI-6-Pad45)") (class "Default")
      (node (ref "PCB1") (pin "45") (pinfunction "PI-6_45") (pintype "unspecified+no_connect"))
    )
    (net (code "116") (name "unconnected-(PCB1-PI-7-Pad46)") (class "Default")
      (node (ref "PCB1") (pin "46") (pinfunction "PI-7_46") (pintype "unspecified+no_connect"))
    )
    (net (code "117") (name "unconnected-(PCB1-PI-8-Pad47)") (class "Default")
      (node (ref "PCB1") (pin "47") (pinfunction "PI-8_47") (pintype "unspecified+no_connect"))
    )
    (net (code "118") (name "unconnected-(PCB1-PO-5-Pad84)") (class "Default")
      (node (ref "PCB1") (pin "84") (pinfunction "PO-5_84") (pintype "unspecified+no_connect"))
    )
    (net (code "119") (name "unconnected-(PCB1-PO-6-Pad85)") (class "Default")
      (node (ref "PCB1") (pin "85") (pinfunction "PO-6_85") (pintype "unspecified+no_connect"))
    )
    (net (code "120") (name "unconnected-(PCB1-PO-7-Pad86)") (class "Default")
      (node (ref "PCB1") (pin "86") (pinfunction "PO-7_86") (pintype "unspecified+no_connect"))
    )
    (net (code "121") (name "unconnected-(PCB1-PO-8-Pad87)") (class "Default")
      (node (ref "PCB1") (pin "87") (pinfunction "PO-8_87") (pintype "unspecified+no_connect"))
    )
    (net (code "122") (name "unconnected-(U1-INT#-Pad1)") (class "Default")
      (node (ref "U1") (pin "1") (pinfunction "INT#_1") (pintype "unspecified+no_connect"))
    )
    (net (code "123") (name "unconnected-(U2-OUTB-Pad4)") (class "Default")
      (node (ref "U2") (pin "4") (pinfunction "OUTB_4") (pintype "unspecified+no_connect"))
    )
    (net (code "124") (name "unconnected-(U4-INT#-Pad1)") (class "Default")
      (node (ref "U4") (pin "1") (pinfunction "INT#_1") (pintype "unspecified+no_connect"))
    )
  )
)
